# 13_-KB_CONNECTORS.net
KiCad netlist of a schematic drawn in Altium Designer
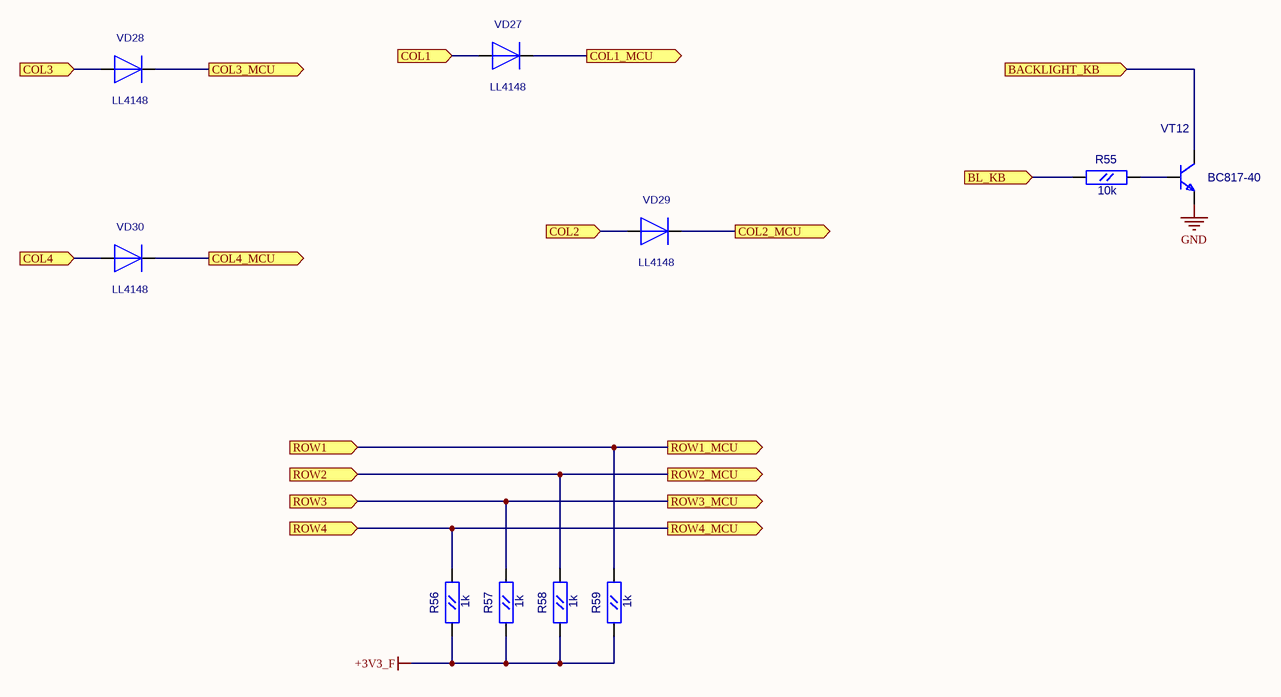
[diagram p0: [13]-KB_CONNECTORS.SchDoc]

(export (version "E")
  (design (tool "Eeschema 10.0.6"))
  (components
    (comp (ref "R55")
      (value "10k")
      (footprint "RC0603")
      (description "RC0603")
      (libsource (lib "fizik_lib") (part "RC0603"))
    )
    (comp (ref "R56")
      (value "1k")
      (footprint "RC0603")
      (description "RC0603")
      (libsource (lib "fizik_lib") (part "RC0603"))
    )
    (comp (ref "R57")
      (value "1k")
      (footprint "RC0603")
      (description "RC0603")
      (libsource (lib "fizik_lib") (part "RC0603"))
    )
    (comp (ref "R58")
      (value "1k")
      (footprint "RC0603")
      (description "RC0603")
      (libsource (lib "fizik_lib") (part "RC0603"))
    )
    (comp (ref "R59")
      (value "1k")
      (footprint "RC0603")
      (description "RC0603")
      (libsource (lib "fizik_lib") (part "RC0603"))
    )
    (comp (ref "VD27") (value "LL4148") (footprint "SOD-80") (libsource (lib "fizik_lib") (part "LL4148")))
    (comp (ref "VD28") (value "LL4148") (footprint "SOD-80") (libsource (lib "fizik_lib") (part "LL4148")))
    (comp (ref "VD29") (value "LL4148") (footprint "SOD-80") (libsource (lib "fizik_lib") (part "LL4148")))
    (comp (ref "VD30") (value "LL4148") (footprint "SOD-80") (libsource (lib "fizik_lib") (part "LL4148")))
    (comp (ref "VT12")
      (value "BC817-40")
      (footprint "SOT-23(123)")
      (description "NPN 500ma transistor")
      (libsource (lib "fizik_lib") (part "BC846BLT1"))
    )
  )
  (nets
    (net (code "1") (name "+3V3_F") (class "Default")
      (node (ref "R56") (pin "1") (pinfunction "A_1") (pintype "passive"))
      (node (ref "R57") (pin "1") (pinfunction "A_1") (pintype "passive"))
      (node (ref "R58") (pin "1") (pinfunction "A_1") (pintype "passive"))
      (node (ref "R59") (pin "1") (pinfunction "A_1") (pintype "passive"))
    )
    (net (code "2") (name "/BACKLIGHT_KB") (class "Default")
      (node (ref "VT12") (pin "3") (pinfunction "C_3") (pintype "passive"))
    )
    (net (code "3") (name "/BL_KB") (class "Default")
      (node (ref "R55") (pin "1") (pinfunction "A_1") (pintype "passive"))
    )
    (net (code "4") (name "/COL1") (class "Default")
      (node (ref "VD27") (pin "1") (pinfunction "-_1") (pintype "passive"))
    )
    (net (code "5") (name "/COL1_MCU") (class "Default")
      (node (ref "VD27") (pin "2") (pinfunction "+_2") (pintype "passive"))
    )
    (net (code "6") (name "/COL2") (class "Default")
      (node (ref "VD29") (pin "1") (pinfunction "-_1") (pintype "passive"))
    )
    (net (code "7") (name "/COL2_MCU") (class "Default")
      (node (ref "VD29") (pin "2") (pinfunction "+_2") (pintype "passive"))
    )
    (net (code "8") (name "/COL3") (class "Default")
      (node (ref "VD28") (pin "1") (pinfunction "-_1") (pintype "passive"))
    )
    (net (code "9") (name "/COL3_MCU") (class "Default")
      (node (ref "VD28") (pin "2") (pinfunction "+_2") (pintype "passive"))
    )
    (net (code "10") (name "/COL4") (class "Default")
      (node (ref "VD30") (pin "1") (pinfunction "-_1") (pintype "passive"))
    )
    (net (code "11") (name "/COL4_MCU") (class "Default")
      (node (ref "VD30") (pin "2") (pinfunction "+_2") (pintype "passive"))
    )
    (net (code "12") (name "/ROW1") (class "Default")
      (node (ref "R59") (pin "2") (pinfunction "B_2") (pintype "passive"))
    )
    (net (code "13") (name "/ROW2") (class "Default")
      (node (ref "R58") (pin "2") (pinfunction "B_2") (pintype "passive"))
    )
    (net (code "14") (name "/ROW3") (class "Default")
      (node (ref "R57") (pin "2") (pinfunction "B_2") (pintype "passive"))
    )
    (net (code "15") (name "/ROW4") (class "Default")
      (node (ref "R56") (pin "2") (pinfunction "B_2") (pintype "passive"))
    )
    (net (code "16") (name "GND") (class "Default")
      (node (ref "VT12") (pin "2") (pinfunction "E_2") (pintype "passive"))
    )
    (net (code "17") (name "Net-(R55-B)") (class "Default")
      (node (ref "R55") (pin "2") (pinfunction "B_2") (pintype "passive"))
      (node (ref "VT12") (pin "1") (pinfunction "B_1") (pintype "passive"))
    )
  )
)
